# debug.net
KiCad netlist of a schematic drawn in Altium Designer
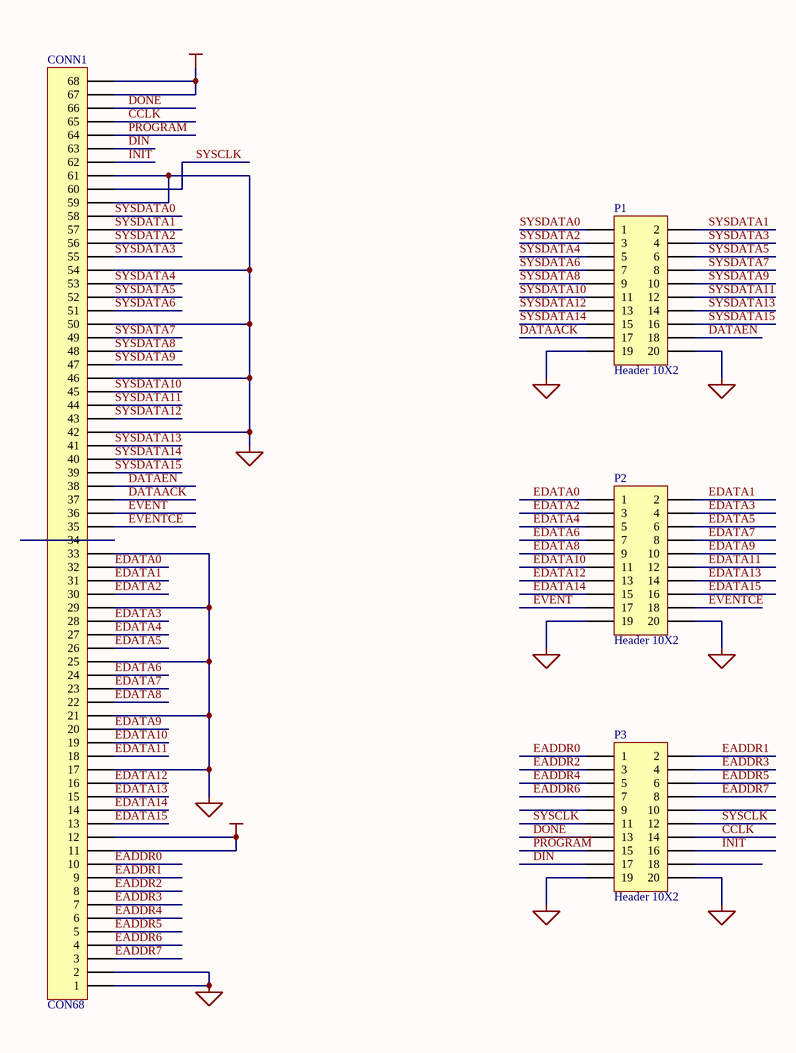
[diagram p0: debug.SCHDOC]

(export (version "E")
  (design (tool "Eeschema 10.0.6"))
  (components
    (comp (ref "CONN1")
      (value "CON68")
      (footprint "MOLEX 71661-2068")
      (libsource (lib "My devices") (part "CON68"))
    )
    (comp (ref "P1")
      (value "Header 10X2")
      (footprint "HDR2X10")
      (description "Header, 10-Pin, Dual row")
      (fields (field (name "PUBLISHER") "Altium Limited"))
      (libsource (lib "Miscellaneous Connectors") (part "Header 10X2"))
    )
    (comp (ref "P2")
      (value "Header 10X2")
      (footprint "HDR2X10")
      (description "Header, 10-Pin, Dual row")
      (fields (field (name "PUBLISHER") "Altium Limited"))
      (libsource (lib "Miscellaneous Connectors") (part "Header 10X2"))
    )
    (comp (ref "P3")
      (value "Header 10X2")
      (footprint "HDR2X10")
      (description "Header, 10-Pin, Dual row")
      (fields (field (name "PUBLISHER") "Altium Limited"))
      (libsource (lib "Miscellaneous Connectors") (part "Header 10X2"))
    )
  )
  (nets
    (net (code "1") (name "/CCLK") (class "Default")
      (node (ref "CONN1") (pin "65") (pinfunction "65_65") (pintype "passive"))
      (node (ref "P3") (pin "14") (pinfunction "14_14") (pintype "passive"))
    )
    (net (code "2") (name "/DATAACK") (class "Default")
      (node (ref "CONN1") (pin "37") (pinfunction "37_37") (pintype "passive"))
      (node (ref "P1") (pin "17") (pinfunction "17_17") (pintype "passive"))
    )
    (net (code "3") (name "/DATAEN") (class "Default")
      (node (ref "CONN1") (pin "38") (pinfunction "38_38") (pintype "passive"))
      (node (ref "P1") (pin "18") (pinfunction "18_18") (pintype "passive"))
    )
    (net (code "4") (name "/DIN") (class "Default")
      (node (ref "CONN1") (pin "63") (pinfunction "63_63") (pintype "passive"))
      (node (ref "P3") (pin "17") (pinfunction "17_17") (pintype "passive"))
    )
    (net (code "5") (name "/DONE") (class "Default")
      (node (ref "CONN1") (pin "66") (pinfunction "66_66") (pintype "passive"))
      (node (ref "P3") (pin "13") (pinfunction "13_13") (pintype "passive"))
    )
    (net (code "6") (name "/EADDR0") (class "Default")
      (node (ref "CONN1") (pin "10") (pinfunction "10_10") (pintype "passive"))
      (node (ref "P3") (pin "1") (pinfunction "1_1") (pintype "passive"))
    )
    (net (code "7") (name "/EADDR1") (class "Default")
      (node (ref "CONN1") (pin "9") (pinfunction "9_9") (pintype "passive"))
      (node (ref "P3") (pin "2") (pinfunction "2_2") (pintype "passive"))
    )
    (net (code "8") (name "/EADDR2") (class "Default")
      (node (ref "CONN1") (pin "8") (pinfunction "8_8") (pintype "passive"))
      (node (ref "P3") (pin "3") (pinfunction "3_3") (pintype "passive"))
    )
    (net (code "9") (name "/EADDR3") (class "Default")
      (node (ref "CONN1") (pin "7") (pinfunction "7_7") (pintype "passive"))
      (node (ref "P3") (pin "4") (pinfunction "4_4") (pintype "passive"))
    )
    (net (code "10") (name "/EADDR4") (class "Default")
      (node (ref "CONN1") (pin "6") (pinfunction "6_6") (pintype "passive"))
      (node (ref "P3") (pin "5") (pinfunction "5_5") (pintype "passive"))
    )
    (net (code "11") (name "/EADDR5") (class "Default")
      (node (ref "CONN1") (pin "5") (pinfunction "5_5") (pintype "passive"))
      (node (ref "P3") (pin "6") (pinfunction "6_6") (pintype "passive"))
    )
    (net (code "12") (name "/EADDR6") (class "Default")
      (node (ref "CONN1") (pin "4") (pinfunction "4_4") (pintype "passive"))
      (node (ref "P3") (pin "7") (pinfunction "7_7") (pintype "passive"))
    )
    (net (code "13") (name "/EADDR7") (class "Default")
      (node (ref "CONN1") (pin "3") (pinfunction "3_3") (pintype "passive"))
      (node (ref "P3") (pin "8") (pinfunction "8_8") (pintype "passive"))
    )
    (net (code "14") (name "/EDATA0") (class "Default")
      (node (ref "CONN1") (pin "32") (pinfunction "32_32") (pintype "passive"))
      (node (ref "P2") (pin "1") (pinfunction "1_1") (pintype "passive"))
    )
    (net (code "15") (name "/EDATA1") (class "Default")
      (node (ref "CONN1") (pin "31") (pinfunction "31_31") (pintype "passive"))
      (node (ref "P2") (pin "2") (pinfunction "2_2") (pintype "passive"))
    )
    (net (code "16") (name "/EDATA2") (class "Default")
      (node (ref "CONN1") (pin "30") (pinfunction "30_30") (pintype "passive"))
      (node (ref "P2") (pin "3") (pinfunction "3_3") (pintype "passive"))
    )
    (net (code "17") (name "/EDATA3") (class "Default")
      (node (ref "CONN1") (pin "28") (pinfunction "28_28") (pintype "passive"))
      (node (ref "P2") (pin "4") (pinfunction "4_4") (pintype "passive"))
    )
    (net (code "18") (name "/EDATA4") (class "Default")
      (node (ref "CONN1") (pin "27") (pinfunction "27_27") (pintype "passive"))
      (node (ref "P2") (pin "5") (pinfunction "5_5") (pintype "passive"))
    )
    (net (code "19") (name "/EDATA5") (class "Default")
      (node (ref "CONN1") (pin "26") (pinfunction "26_26") (pintype "passive"))
      (node (ref "P2") (pin "6") (pinfunction "6_6") (pintype "passive"))
    )
    (net (code "20") (name "/EDATA6") (class "Default")
      (node (ref "CONN1") (pin "24") (pinfunction "24_24") (pintype "passive"))
      (node (ref "P2") (pin "7") (pinfunction "7_7") (pintype "passive"))
    )
    (net (code "21") (name "/EDATA7") (class "Default")
      (node (ref "CONN1") (pin "23") (pinfunction "23_23") (pintype "passive"))
      (node (ref "P2") (pin "8") (pinfunction "8_8") (pintype "passive"))
    )
    (net (code "22") (name "/EDATA8") (class "Default")
      (node (ref "CONN1") (pin "22") (pinfunction "22_22") (pintype "passive"))
      (node (ref "P2") (pin "9") (pinfunction "9_9") (pintype "passive"))
    )
    (net (code "23") (name "/EDATA9") (class "Default")
      (node (ref "CONN1") (pin "20") (pinfunction "20_20") (pintype "passive"))
      (node (ref "P2") (pin "10") (pinfunction "10_10") (pintype "passive"))
    )
    (net (code "24") (name "/EDATA10") (class "Default")
      (node (ref "CONN1") (pin "19") (pinfunction "19_19") (pintype "passive"))
      (node (ref "P2") (pin "11") (pinfunction "11_11") (pintype "passive"))
    )
    (net (code "25") (name "/EDATA11") (class "Default")
      (node (ref "CONN1") (pin "18") (pinfunction "18_18") (pintype "passive"))
      (node (ref "P2") (pin "12") (pinfunction "12_12") (pintype "passive"))
    )
    (net (code "26") (name "/EDATA12") (class "Default")
      (node (ref "CONN1") (pin "16") (pinfunction "16_16") (pintype "passive"))
      (node (ref "P2") (pin "13") (pinfunction "13_13") (pintype "passive"))
    )
    (net (code "27") (name "/EDATA13") (class "Default")
      (node (ref "CONN1") (pin "15") (pinfunction "15_15") (pintype "passive"))
      (node (ref "P2") (pin "14") (pinfunction "14_14") (pintype "passive"))
    )
    (net (code "28") (name "/EDATA14") (class "Default")
      (node (ref "CONN1") (pin "14") (pinfunction "14_14") (pintype "passive"))
      (node (ref "P2") (pin "15") (pinfunction "15_15") (pintype "passive"))
    )
    (net (code "29") (name "/EDATA15") (class "Default")
      (node (ref "CONN1") (pin "13") (pinfunction "13_13") (pintype "passive"))
      (node (ref "P2") (pin "16") (pinfunction "16_16") (pintype "passive"))
    )
    (net (code "30") (name "/EVENT") (class "Default")
      (node (ref "CONN1") (pin "36") (pinfunction "36_36") (pintype "passive"))
      (node (ref "P2") (pin "17") (pinfunction "17_17") (pintype "passive"))
    )
    (net (code "31") (name "/EVENTCE") (class "Default")
      (node (ref "CONN1") (pin "35") (pinfunction "35_35") (pintype "passive"))
      (node (ref "P2") (pin "18") (pinfunction "18_18") (pintype "passive"))
    )
    (net (code "32") (name "/INIT") (class "Default")
      (node (ref "CONN1") (pin "62") (pinfunction "62_62") (pintype "passive"))
      (node (ref "P3") (pin "16") (pinfunction "16_16") (pintype "passive"))
    )
    (net (code "33") (name "/SYSCLK") (class "Default")
      (node (ref "CONN1") (pin "60") (pinfunction "60_60") (pintype "passive"))
      (node (ref "P3") (pin "11") (pinfunction "11_11") (pintype "passive"))
      (node (ref "P3") (pin "12") (pinfunction "12_12") (pintype "passive"))
    )
    (net (code "34") (name "/SYSDATA0") (class "Default")
      (node (ref "CONN1") (pin "58") (pinfunction "58_58") (pintype "passive"))
      (node (ref "P1") (pin "1") (pinfunction "1_1") (pintype "passive"))
    )
    (net (code "35") (name "/SYSDATA1") (class "Default")
      (node (ref "CONN1") (pin "57") (pinfunction "57_57") (pintype "passive"))
      (node (ref "P1") (pin "2") (pinfunction "2_2") (pintype "passive"))
    )
    (net (code "36") (name "/SYSDATA2") (class "Default")
      (node (ref "CONN1") (pin "56") (pinfunction "56_56") (pintype "passive"))
      (node (ref "P1") (pin "3") (pinfunction "3_3") (pintype "passive"))
    )
    (net (code "37") (name "/SYSDATA3") (class "Default")
      (node (ref "CONN1") (pin "55") (pinfunction "55_55") (pintype "passive"))
      (node (ref "P1") (pin "4") (pinfunction "4_4") (pintype "passive"))
    )
    (net (code "38") (name "/SYSDATA4") (class "Default")
      (node (ref "CONN1") (pin "53") (pinfunction "53_53") (pintype "passive"))
      (node (ref "P1") (pin "5") (pinfunction "5_5") (pintype "passive"))
    )
    (net (code "39") (name "/SYSDATA5") (class "Default")
      (node (ref "CONN1") (pin "52") (pinfunction "52_52") (pintype "passive"))
      (node (ref "P1") (pin "6") (pinfunction "6_6") (pintype "passive"))
    )
    (net (code "40") (name "/SYSDATA6") (class "Default")
      (node (ref "CONN1") (pin "51") (pinfunction "51_51") (pintype "passive"))
      (node (ref "P1") (pin "7") (pinfunction "7_7") (pintype "passive"))
    )
    (net (code "41") (name "/SYSDATA7") (class "Default")
      (node (ref "CONN1") (pin "49") (pinfunction "49_49") (pintype "passive"))
      (node (ref "P1") (pin "8") (pinfunction "8_8") (pintype "passive"))
    )
    (net (code "42") (name "/SYSDATA8") (class "Default")
      (node (ref "CONN1") (pin "48") (pinfunction "48_48") (pintype "passive"))
      (node (ref "P1") (pin "9") (pinfunction "9_9") (pintype "passive"))
    )
    (net (code "43") (name "/SYSDATA9") (class "Default")
      (node (ref "CONN1") (pin "47") (pinfunction "47_47") (pintype "passive"))
      (node (ref "P1") (pin "10") (pinfunction "10_10") (pintype "passive"))
    )
    (net (code "44") (name "/SYSDATA10") (class "Default")
      (node (ref "CONN1") (pin "45") (pinfunction "45_45") (pintype "passive"))
      (node (ref "P1") (pin "11") (pinfunction "11_11") (pintype "passive"))
    )
    (net (code "45") (name "/SYSDATA11") (class "Default")
      (node (ref "CONN1") (pin "44") (pinfunction "44_44") (pintype "passive"))
      (node (ref "P1") (pin "12") (pinfunction "12_12") (pintype "passive"))
    )
    (net (code "46") (name "/SYSDATA12") (class "Default")
      (node (ref "CONN1") (pin "43") (pinfunction "43_43") (pintype "passive"))
      (node (ref "P1") (pin "13") (pinfunction "13_13") (pintype "passive"))
    )
    (net (code "47") (name "/SYSDATA13") (class "Default")
      (node (ref "CONN1") (pin "41") (pinfunction "41_41") (pintype "passive"))
      (node (ref "P1") (pin "14") (pinfunction "14_14") (pintype "passive"))
    )
    (net (code "48") (name "/SYSDATA14") (class "Default")
      (node (ref "CONN1") (pin "40") (pinfunction "40_40") (pintype "passive"))
      (node (ref "P1") (pin "15") (pinfunction "15_15") (pintype "passive"))
    )
    (net (code "49") (name "/SYSDATA15") (class "Default")
      (node (ref "CONN1") (pin "39") (pinfunction "39_39") (pintype "passive"))
      (node (ref "P1") (pin "16") (pinfunction "16_16") (pintype "passive"))
    )
    (net (code "50") (name "/~{PROGRAM}") (class "Default")
      (node (ref "CONN1") (pin "64") (pinfunction "64_64") (pintype "passive"))
      (node (ref "P3") (pin "15") (pinfunction "15_15") (pintype "passive"))
    )
    (net (code "51") (name "GND") (class "Default")
      (node (ref "CONN1") (pin "1") (pinfunction "1_1") (pintype "passive"))
      (node (ref "CONN1") (pin "17") (pinfunction "17_17") (pintype "passive"))
      (node (ref "CONN1") (pin "2") (pinfunction "2_2") (pintype "passive"))
      (node (ref "CONN1") (pin "21") (pinfunction "21_21") (pintype "passive"))
      (node (ref "CONN1") (pin "25") (pinfunction "25_25") (pintype "passive"))
      (node (ref "CONN1") (pin "29") (pinfunction "29_29") (pintype "passive"))
      (node (ref "CONN1") (pin "33") (pinfunction "33_33") (pintype "passive"))
      (node (ref "CONN1") (pin "42") (pinfunction "42_42") (pintype "passive"))
      (node (ref "CONN1") (pin "46") (pinfunction "46_46") (pintype "passive"))
      (node (ref "CONN1") (pin "50") (pinfunction "50_50") (pintype "passive"))
      (node (ref "CONN1") (pin "54") (pinfunction "54_54") (pintype "passive"))
      (node (ref "CONN1") (pin "59") (pinfunction "59_59") (pintype "passive"))
      (node (ref "CONN1") (pin "61") (pinfunction "61_61") (pintype "passive"))
      (node (ref "P1") (pin "19") (pinfunction "19_19") (pintype "passive"))
      (node (ref "P1") (pin "20") (pinfunction "20_20") (pintype "passive"))
      (node (ref "P2") (pin "19") (pinfunction "19_19") (pintype "passive"))
      (node (ref "P2") (pin "20") (pinfunction "20_20") (pintype "passive"))
      (node (ref "P3") (pin "19") (pinfunction "19_19") (pintype "passive"))
      (node (ref "P3") (pin "20") (pinfunction "20_20") (pintype "passive"))
    )
    (net (code "52") (name "VCC") (class "Default")
      (node (ref "CONN1") (pin "11") (pinfunction "11_11") (pintype "passive"))
      (node (ref "CONN1") (pin "12") (pinfunction "12_12") (pintype "passive"))
      (node (ref "CONN1") (pin "67") (pinfunction "67_67") (pintype "passive"))
      (node (ref "CONN1") (pin "68") (pinfunction "68_68") (pintype "passive"))
    )
    (net (code "53") (name "unconnected-(CONN1-Pad34)") (class "Default")
      (node (ref "CONN1") (pin "34") (pinfunction "34_34") (pintype "passive"))
    )
    (net (code "54") (name "unconnected-(P3-Pad9)") (class "Default")
      (node (ref "P3") (pin "9") (pinfunction "9_9") (pintype "passive"))
    )
    (net (code "55") (name "unconnected-(P3-Pad10)") (class "Default")
      (node (ref "P3") (pin "10") (pinfunction "10_10") (pintype "passive"))
    )
    (net (code "56") (name "unconnected-(P3-Pad18)") (class "Default")
      (node (ref "P3") (pin "18") (pinfunction "18_18") (pintype "passive"))
    )
  )
)
